# D5035-05.net
KiCad netlist of a schematic drawn in Altium Designer
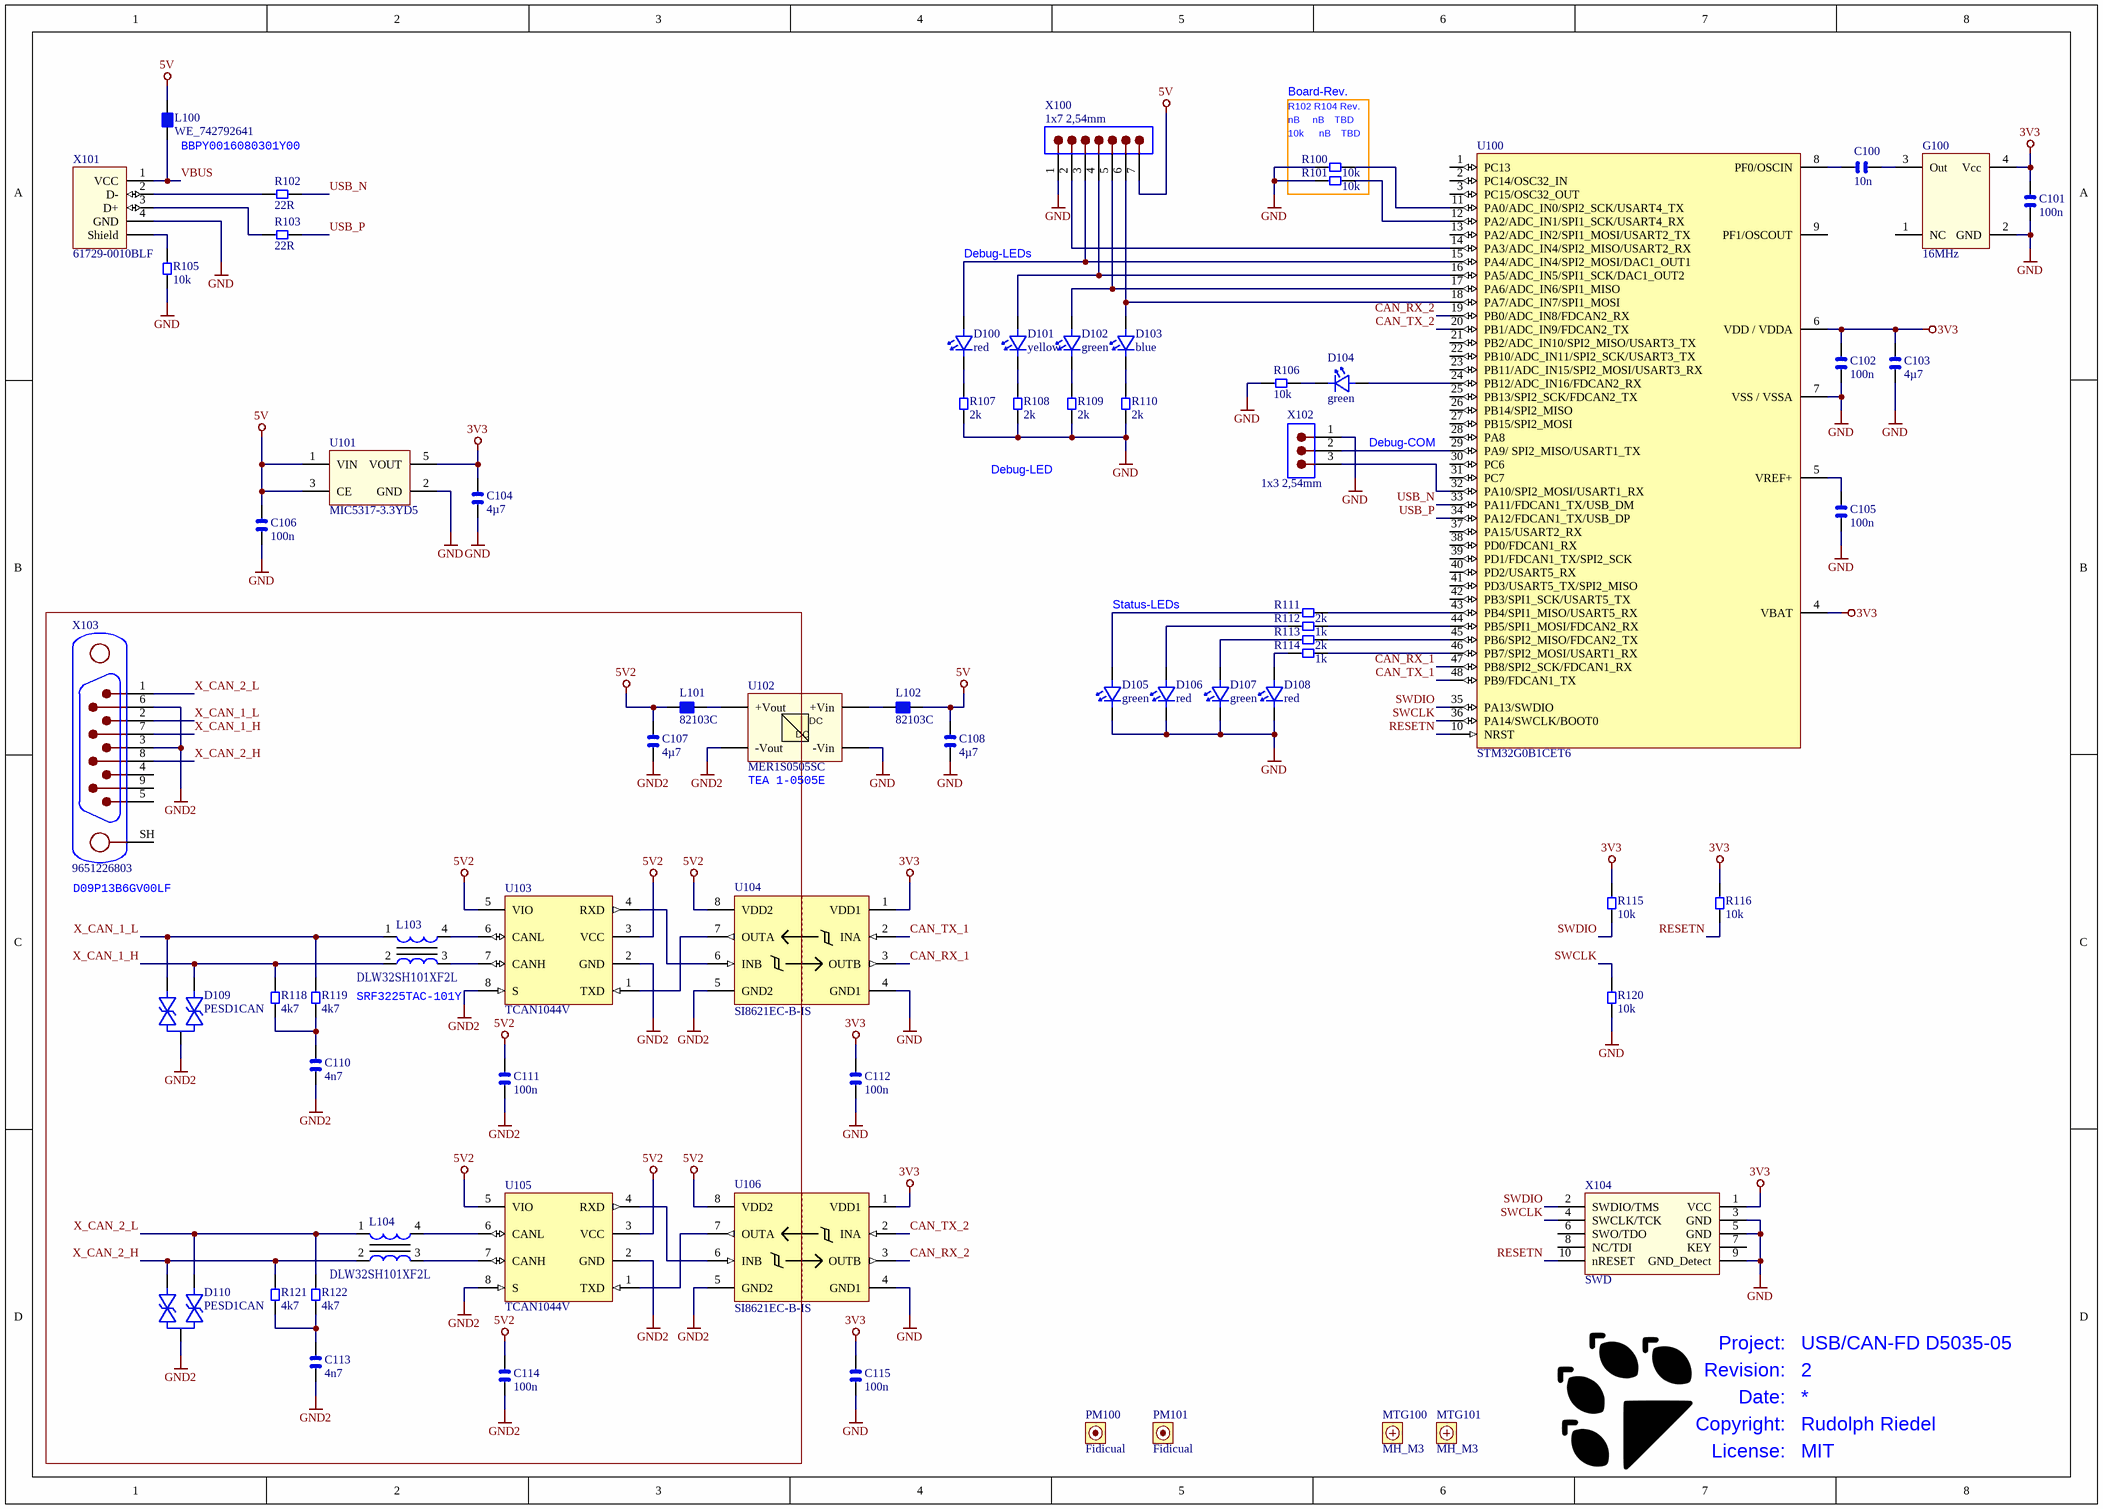
[diagram p0: D5035-05.SchDoc]

(export (version "E")
  (design (tool "Eeschema 10.0.6"))
  (components
    (comp (ref "C100")
      (value "10n")
      (footprint "CAPC1608X09L")
      (description "0603 Chip Capacitor")
      (fields (field (name "PART NUMBER") "CAPC_0603") (field (name "EDITOR") "rriedel"))
      (libsource (lib "HW-Labor_GF") (part "CAP_2_V2"))
    )
    (comp (ref "C101")
      (value "100n")
      (footprint "CAPC1608X09L")
      (description "0603 Chip Capacitor")
      (fields (field (name "PART NUMBER") "CAPC_0603") (field (name "EDITOR") "rriedel"))
      (libsource (lib "HW-Labor_GF") (part "CAP_2_V2"))
    )
    (comp (ref "C102")
      (value "100n")
      (footprint "CAPC1608X09L")
      (description "0603 Chip Capacitor")
      (fields (field (name "PART NUMBER") "CAPC_0603") (field (name "EDITOR") "rriedel"))
      (libsource (lib "HW-Labor_GF") (part "CAP_2_V2"))
    )
    (comp (ref "C103")
      (value "4µ7")
      (footprint "CAPC2012X14L")
      (description "0805 Chip Capacitor")
      (fields (field (name "PART NUMBER") "CAPC_0805") (field (name "EDITOR") "rriedel"))
      (libsource (lib "HW-Labor_GF") (part "CAP_2_V2"))
    )
    (comp (ref "C104")
      (value "4µ7")
      (footprint "CAPC2012X14L")
      (description "0805 Chip Capacitor")
      (fields (field (name "PART NUMBER") "CAPC_0805") (field (name "EDITOR") "rriedel"))
      (libsource (lib "HW-Labor_GF") (part "CAP_2_V2"))
    )
    (comp (ref "C105")
      (value "100n")
      (footprint "CAPC1608X09L")
      (description "0603 Chip Capacitor")
      (fields (field (name "PART NUMBER") "CAPC_0603") (field (name "EDITOR") "rriedel"))
      (libsource (lib "HW-Labor_GF") (part "CAP_2_V2"))
    )
    (comp (ref "C106")
      (value "100n")
      (footprint "CAPC1608X09L")
      (description "0603 Chip Capacitor")
      (fields (field (name "PART NUMBER") "CAPC_0603") (field (name "EDITOR") "rriedel"))
      (libsource (lib "HW-Labor_GF") (part "CAP_2_V2"))
    )
    (comp (ref "C107")
      (value "4µ7")
      (footprint "CAPC2012X14L")
      (description "0805 Chip Capacitor")
      (fields (field (name "PART NUMBER") "CAPC_0805") (field (name "EDITOR") "rriedel"))
      (libsource (lib "HW-Labor_GF") (part "CAP_2_V2"))
    )
    (comp (ref "C108")
      (value "4µ7")
      (footprint "CAPC2012X14L")
      (description "0805 Chip Capacitor")
      (fields (field (name "PART NUMBER") "CAPC_0805") (field (name "EDITOR") "rriedel"))
      (libsource (lib "HW-Labor_GF") (part "CAP_2_V2"))
    )
    (comp (ref "C110")
      (value "4n7")
      (footprint "CAPC2012X14L")
      (description "0805 Chip Capacitor")
      (fields (field (name "PART NUMBER") "CAPC_0805") (field (name "EDITOR") "rriedel"))
      (libsource (lib "HW-Labor_GF") (part "CAP_2_V2"))
    )
    (comp (ref "C111")
      (value "100n")
      (footprint "CAPC1608X09L")
      (description "0603 Chip Capacitor")
      (fields (field (name "PART NUMBER") "CAPC_0603") (field (name "EDITOR") "rriedel"))
      (libsource (lib "HW-Labor_GF") (part "CAP_2_V2"))
    )
    (comp (ref "C112")
      (value "100n")
      (footprint "CAPC1608X09L")
      (description "0603 Chip Capacitor")
      (fields (field (name "PART NUMBER") "CAPC_0603") (field (name "EDITOR") "rriedel"))
      (libsource (lib "HW-Labor_GF") (part "CAP_2_V2"))
    )
    (comp (ref "C113")
      (value "4n7")
      (footprint "CAPC2012X14L")
      (description "0805 Chip Capacitor")
      (fields (field (name "PART NUMBER") "CAPC_0805") (field (name "EDITOR") "rriedel"))
      (libsource (lib "HW-Labor_GF") (part "CAP_2_V2"))
    )
    (comp (ref "C114")
      (value "100n")
      (footprint "CAPC1608X09L")
      (description "0603 Chip Capacitor")
      (fields (field (name "PART NUMBER") "CAPC_0603") (field (name "EDITOR") "rriedel"))
      (libsource (lib "HW-Labor_GF") (part "CAP_2_V2"))
    )
    (comp (ref "C115")
      (value "100n")
      (footprint "CAPC1608X09L")
      (description "0603 Chip Capacitor")
      (fields (field (name "PART NUMBER") "CAPC_0603") (field (name "EDITOR") "rriedel"))
      (libsource (lib "HW-Labor_GF") (part "CAP_2_V2"))
    )
    (comp (ref "D100")
      (value "red")
      (footprint "DIOC1608X06N_LED")
      (description "LED, 0603")
      (fields (field (name "PART NUMBER") "LED_0603") (field (name "EDITOR") "rriedel"))
      (libsource (lib "HW-Labor_GF") (part "LED_generic"))
    )
    (comp (ref "D101")
      (value "yellow")
      (footprint "DIOC1608X06N_LED")
      (description "LED, 0603")
      (fields (field (name "PART NUMBER") "LED_0603") (field (name "EDITOR") "rriedel"))
      (libsource (lib "HW-Labor_GF") (part "LED_generic"))
    )
    (comp (ref "D102")
      (value "green")
      (footprint "DIOC1608X06N_LED")
      (description "LED, 0603")
      (fields (field (name "PART NUMBER") "LED_0603") (field (name "EDITOR") "rriedel"))
      (libsource (lib "HW-Labor_GF") (part "LED_generic"))
    )
    (comp (ref "D103")
      (value "blue")
      (footprint "DIOC1608X06N_LED")
      (description "LED, 0603")
      (fields (field (name "PART NUMBER") "LED_0603") (field (name "EDITOR") "rriedel"))
      (libsource (lib "HW-Labor_GF") (part "LED_generic"))
    )
    (comp (ref "D104")
      (value "green")
      (footprint "DIOC1608X06N_LED")
      (description "LED, 0603")
      (fields (field (name "PART NUMBER") "LED_0603") (field (name "EDITOR") "rriedel"))
      (libsource (lib "HW-Labor_GF") (part "LED_generic"))
    )
    (comp (ref "D105")
      (value "green")
      (footprint "DIOC1608X06N_LED")
      (description "LED, 0603")
      (fields (field (name "PART NUMBER") "LED_0603") (field (name "EDITOR") "rriedel"))
      (libsource (lib "HW-Labor_GF") (part "LED_generic"))
    )
    (comp (ref "D106")
      (value "red")
      (footprint "DIOC1608X06N_LED")
      (description "LED, 0603")
      (fields (field (name "PART NUMBER") "LED_0603") (field (name "EDITOR") "rriedel"))
      (libsource (lib "HW-Labor_GF") (part "LED_generic"))
    )
    (comp (ref "D107")
      (value "green")
      (footprint "DIOC1608X06N_LED")
      (description "LED, 0603")
      (fields (field (name "PART NUMBER") "LED_0603") (field (name "EDITOR") "rriedel"))
      (libsource (lib "HW-Labor_GF") (part "LED_generic"))
    )
    (comp (ref "D108")
      (value "red")
      (footprint "DIOC1608X06N_LED")
      (description "LED, 0603")
      (fields (field (name "PART NUMBER") "LED_0603") (field (name "EDITOR") "rriedel"))
      (libsource (lib "HW-Labor_GF") (part "LED_generic"))
    )
    (comp (ref "D109")
      (value "PESD1CAN")
      (footprint "SOT95P280X110-3N")
      (description "CAN bus ESD protection diode")
      (fields
        (field (name "MANUFACTURER") "Nexperia")
        (field (name "DISTRIBUTOR_1_PART_NUMBER") "1727-3817-1-ND")
        (field (name "EDITOR") "rriedel")
      )
      (libsource (lib "HW-Labor_GF") (part "PESD1CAN"))
    )
    (comp (ref "D110")
      (value "PESD1CAN")
      (footprint "SOT95P280X110-3N")
      (description "CAN bus ESD protection diode")
      (fields
        (field (name "MANUFACTURER") "Nexperia")
        (field (name "DISTRIBUTOR_1_PART_NUMBER") "1727-3817-1-ND")
        (field (name "EDITOR") "rriedel")
      )
      (libsource (lib "HW-Labor_GF") (part "PESD1CAN"))
    )
    (comp (ref "G100")
      (value "16MHz")
      (footprint "TG2520")
      (description "16MHz Oscillator, +/- 0.5ppm")
      (fields
        (field (name "PART NUMBER") "TG2520SMN16.0000M-MCGNNM")
        (field (name "MANUFACTURER") "Epson")
        (field (name "EDITOR") "rriedel")
      )
      (libsource (lib "HW-Labor_GF") (part "TG2520"))
    )
    (comp (ref "L100")
      (value "WE_742792641")
      (footprint "INDC1608X06L")
      (description "SMT EMI suppression ferrite bead WE-CBF")
      (fields
        (field (name "MANUFACTURER") "Wuerth")
        (field (name "DISTRIBUTOR_1_PART_NUMBER") "732-1592-1-ND")
        (field (name "EDITOR") "rriedel")
      )
      (libsource (lib "HW-Labor_GF") (part "IND_2_V1"))
    )
    (comp (ref "L101")
      (value "82103C")
      (footprint "Murata_8200C")
      (description "10µH, 0,5A, 400mR")
      (fields
        (field (name "MANUFACTURER") "Murata")
        (field (name "DISTRIBUTOR_1_PART_NUMBER") "811-2473-1-ND")
        (field (name "EDITOR") "rriedel")
      )
      (libsource (lib "HW-Labor_GF") (part "IND_2_V1"))
    )
    (comp (ref "L102")
      (value "82103C")
      (footprint "Murata_8200C")
      (description "10µH, 0,5A, 400mR")
      (fields
        (field (name "MANUFACTURER") "Murata")
        (field (name "DISTRIBUTOR_1_PART_NUMBER") "811-2473-1-ND")
        (field (name "EDITOR") "rriedel")
      )
      (libsource (lib "HW-Labor_GF") (part "IND_2_V1"))
    )
    (comp (ref "L103")
      (value "DLW32SH101XF2L‎")
      (footprint "ACT1210")
      (description "Common Mode Filter,  -50°C ... +150°C, AEC-Q200")
      (fields
        (field (name "PART NUMBER") "ACT1210-101-2P-TL00")
        (field (name "MANUFACTURER") "TDK")
        (field (name "EDITOR") "rriedel")
      )
      (libsource (lib "HW-Labor_GF") (part "CAN_DROSSEL"))
    )
    (comp (ref "L104")
      (value "DLW32SH101XF2L‎")
      (footprint "ACT1210")
      (description "Common Mode Filter,  -50°C ... +150°C, AEC-Q200")
      (fields
        (field (name "PART NUMBER") "ACT1210-101-2P-TL00")
        (field (name "MANUFACTURER") "TDK")
        (field (name "EDITOR") "rriedel")
      )
      (libsource (lib "HW-Labor_GF") (part "CAN_DROSSEL"))
    )
    (comp (ref "MTG100")
      (value "MH_M3")
      (footprint "HOLE_3_2MM")
      (description "Mounting-Hole for M3 screws")
      (fields (field (name "EDITOR") "rriedel"))
      (libsource (lib "HW-Labor_GF") (part "MTG_V1"))
    )
    (comp (ref "MTG101")
      (value "MH_M3")
      (footprint "HOLE_3_2MM")
      (description "Mounting-Hole for M3 screws")
      (fields (field (name "EDITOR") "rriedel"))
      (libsource (lib "HW-Labor_GF") (part "MTG_V1"))
    )
    (comp (ref "PM100")
      (value "Fidicual")
      (footprint "PM100")
      (fields (field (name "PART NUMBER") "PM100") (field (name "EDITOR") "rriedel"))
      (libsource (lib "HW-Labor_GF") (part "PM100"))
    )
    (comp (ref "PM101")
      (value "Fidicual")
      (footprint "PM100")
      (fields (field (name "PART NUMBER") "PM100") (field (name "EDITOR") "rriedel"))
      (libsource (lib "HW-Labor_GF") (part "PM100"))
    )
    (comp (ref "R100")
      (value "10k")
      (footprint "RESC1608X06L")
      (description "0603 Chip Resistor")
      (fields (field (name "PART NUMBER") "RESC_0603") (field (name "EDITOR") "rriedel"))
      (libsource (lib "HW-Labor_GF") (part "RES_2_V2"))
    )
    (comp (ref "R101")
      (value "10k")
      (footprint "RESC1608X06L")
      (description "0603 Chip Resistor")
      (fields (field (name "PART NUMBER") "RESC_0603") (field (name "EDITOR") "rriedel"))
      (libsource (lib "HW-Labor_GF") (part "RES_2_V2"))
    )
    (comp (ref "R102")
      (value "22R")
      (footprint "RESC1608X06L")
      (description "0603 Chip Resistor")
      (fields (field (name "PART NUMBER") "RESC_0603") (field (name "EDITOR") "rriedel"))
      (libsource (lib "HW-Labor_GF") (part "RES_2_V2"))
    )
    (comp (ref "R103")
      (value "22R")
      (footprint "RESC1608X06L")
      (description "0603 Chip Resistor")
      (fields (field (name "PART NUMBER") "RESC_0603") (field (name "EDITOR") "rriedel"))
      (libsource (lib "HW-Labor_GF") (part "RES_2_V2"))
    )
    (comp (ref "R105")
      (value "10k")
      (footprint "RESC1608X06L")
      (description "0603 Chip Resistor")
      (fields (field (name "PART NUMBER") "RESC_0603") (field (name "EDITOR") "rriedel"))
      (libsource (lib "HW-Labor_GF") (part "RES_2_V2"))
    )
    (comp (ref "R106")
      (value "10k")
      (footprint "RESC1608X06L")
      (description "0603 Chip Resistor")
      (fields (field (name "PART NUMBER") "RESC_0603") (field (name "EDITOR") "rriedel"))
      (libsource (lib "HW-Labor_GF") (part "RES_2_V2"))
    )
    (comp (ref "R107")
      (value "2k")
      (footprint "RESC1608X06L")
      (description "0603 Chip Resistor")
      (fields (field (name "PART NUMBER") "RESC_0603") (field (name "EDITOR") "rriedel"))
      (libsource (lib "HW-Labor_GF") (part "RES_2_V2"))
    )
    (comp (ref "R108")
      (value "2k")
      (footprint "RESC1608X06L")
      (description "0603 Chip Resistor")
      (fields (field (name "PART NUMBER") "RESC_0603") (field (name "EDITOR") "rriedel"))
      (libsource (lib "HW-Labor_GF") (part "RES_2_V2"))
    )
    (comp (ref "R109")
      (value "2k")
      (footprint "RESC1608X06L")
      (description "0603 Chip Resistor")
      (fields (field (name "PART NUMBER") "RESC_0603") (field (name "EDITOR") "rriedel"))
      (libsource (lib "HW-Labor_GF") (part "RES_2_V2"))
    )
    (comp (ref "R110")
      (value "2k")
      (footprint "RESC1608X06L")
      (description "0603 Chip Resistor")
      (fields (field (name "PART NUMBER") "RESC_0603") (field (name "EDITOR") "rriedel"))
      (libsource (lib "HW-Labor_GF") (part "RES_2_V2"))
    )
    (comp (ref "R111")
      (value "2k")
      (footprint "RESC1608X06L")
      (description "0603 Chip Resistor")
      (fields (field (name "PART NUMBER") "RESC_0603") (field (name "EDITOR") "rriedel"))
      (libsource (lib "HW-Labor_GF") (part "RES_2_V2"))
    )
    (comp (ref "R112")
      (value "1k")
      (footprint "RESC1608X06L")
      (description "0603 Chip Resistor")
      (fields (field (name "PART NUMBER") "RESC_0603") (field (name "EDITOR") "rriedel"))
      (libsource (lib "HW-Labor_GF") (part "RES_2_V2"))
    )
    (comp (ref "R113")
      (value "2k")
      (footprint "RESC1608X06L")
      (description "0603 Chip Resistor")
      (fields (field (name "PART NUMBER") "RESC_0603") (field (name "EDITOR") "rriedel"))
      (libsource (lib "HW-Labor_GF") (part "RES_2_V2"))
    )
    (comp (ref "R114")
      (value "1k")
      (footprint "RESC1608X06L")
      (description "0603 Chip Resistor")
      (fields (field (name "PART NUMBER") "RESC_0603") (field (name "EDITOR") "rriedel"))
      (libsource (lib "HW-Labor_GF") (part "RES_2_V2"))
    )
    (comp (ref "R115")
      (value "10k")
      (footprint "RESC1608X06L")
      (description "0603 Chip Resistor")
      (fields (field (name "PART NUMBER") "RESC_0603") (field (name "EDITOR") "rriedel"))
      (libsource (lib "HW-Labor_GF") (part "RES_2_V2"))
    )
    (comp (ref "R116")
      (value "10k")
      (footprint "RESC1608X06L")
      (description "0603 Chip Resistor")
      (fields (field (name "PART NUMBER") "RESC_0603") (field (name "EDITOR") "rriedel"))
      (libsource (lib "HW-Labor_GF") (part "RES_2_V2"))
    )
    (comp (ref "R118")
      (value "4k7")
      (footprint "RESC2012X06L")
      (description "0805 Chip Resistor")
      (fields (field (name "PART NUMBER") "RESC_0805") (field (name "EDITOR") "rriedel"))
      (libsource (lib "HW-Labor_GF") (part "RES_2_V2"))
    )
    (comp (ref "R119")
      (value "4k7")
      (footprint "RESC2012X06L")
      (description "0805 Chip Resistor")
      (fields (field (name "PART NUMBER") "RESC_0805") (field (name "EDITOR") "rriedel"))
      (libsource (lib "HW-Labor_GF") (part "RES_2_V2"))
    )
    (comp (ref "R120")
      (value "10k")
      (footprint "RESC1608X06L")
      (description "0603 Chip Resistor")
      (fields (field (name "PART NUMBER") "RESC_0603") (field (name "EDITOR") "rriedel"))
      (libsource (lib "HW-Labor_GF") (part "RES_2_V2"))
    )
    (comp (ref "R121")
      (value "4k7")
      (footprint "RESC2012X06L")
      (description "0805 Chip Resistor")
      (fields (field (name "PART NUMBER") "RESC_0805") (field (name "EDITOR") "rriedel"))
      (libsource (lib "HW-Labor_GF") (part "RES_2_V2"))
    )
    (comp (ref "R122")
      (value "4k7")
      (footprint "RESC2012X06L")
      (description "0805 Chip Resistor")
      (fields (field (name "PART NUMBER") "RESC_0805") (field (name "EDITOR") "rriedel"))
      (libsource (lib "HW-Labor_GF") (part "RES_2_V2"))
    )
    (comp (ref "U100")
      (value "STM32G0B1CET6")
      (footprint "TQFP50P900X900X120-48N")
      (description "32-bit Microcontroller, 64MHz Cortex M0+, 512k FLASH,  USB")
      (fields
        (field (name "MANUFACTURER") "STM")
        (field (name "DISTRIBUTOR_1_PART_NUMBER") "511-STM32G0B1CET6")
        (field (name "EDITOR") "rriedel")
      )
      (libsource (lib "HW-Labor_GF") (part "STM32G0B1CxTx"))
    )
    (comp (ref "U101")
      (value "MIC5317-3.3YD5")
      (footprint "SOT95P280X110-5N")
      (description "100 mA LDO,  Vout= 3,3V, -40°C..125°C")
      (fields
        (field (name "PART NUMBER") "MIC5233-3.3")
        (field (name "MANUFACTURER") "Microchip")
        (field (name "EDITOR") "rriedel")
      )
      (libsource (lib "HW-Labor_GF") (part "LDO_SOT23-5"))
    )
    (comp (ref "U102")
      (value "MER1S0505SC")
      (footprint "MER1SxxxxC")
      (description "Isolated 1W Single Output DC-DC Converters 5V/5V 200mA")
      (fields
        (field (name "MANUFACTURER") "Murata")
        (field (name "DISTRIBUTOR_1_PART_NUMBER") "811-2124-5-ND‎")
        (field (name "EDITOR") "rriedel")
      )
      (libsource (lib "HW-Labor_GF") (part "MER1SxxxxC"))
    )
    (comp (ref "U103")
      (value "TCAN1044V")
      (footprint "SOT65P280X100-8N")
      (description "CAN-FD transceiver 8MBit, VIO Pin")
      (fields
        (field (name "MANUFACTURER") "TI")
        (field (name "DISTRIBUTOR_1_PART_NUMBER") "296-TCAN1044VDDFRCT-ND")
        (field (name "EDITOR") "rriedel")
      )
      (libsource (lib "HW-Labor_GF") (part "TJA1051T_3"))
    )
    (comp (ref "U104")
      (value "SI8621EC-B-IS")
      (footprint "SOIC127P600X175-8N")
      (description "Dual channel digital isolator, 150Mbit, 3,75kV")
      (fields
        (field (name "MANUFACTURER") "Silicon Labs")
        (field (name "DISTRIBUTOR_1_PART_NUMBER") "336-4776-1-ND")
        (field (name "EDITOR") "rriedel")
      )
      (libsource (lib "HW-Labor_GF") (part "SI8621"))
    )
    (comp (ref "U105")
      (value "TCAN1044V")
      (footprint "SOT65P280X100-8N")
      (description "CAN-FD transceiver 8MBit, VIO Pin")
      (fields
        (field (name "MANUFACTURER") "TI")
        (field (name "DISTRIBUTOR_1_PART_NUMBER") "296-TCAN1044VDDFRCT-ND")
        (field (name "EDITOR") "rriedel")
      )
      (libsource (lib "HW-Labor_GF") (part "TJA1051T_3"))
    )
    (comp (ref "U106")
      (value "SI8621EC-B-IS")
      (footprint "SOIC127P600X175-8N")
      (description "Dual channel digital isolator, 150Mbit, 3,75kV")
      (fields
        (field (name "MANUFACTURER") "Silicon Labs")
        (field (name "DISTRIBUTOR_1_PART_NUMBER") "336-4776-1-ND")
        (field (name "EDITOR") "rriedel")
      )
      (libsource (lib "HW-Labor_GF") (part "SI8621"))
    )
    (comp (ref "X100")
      (value "1x7 2,54mm")
      (footprint "PINH_1x07_2_54mm")
      (description "Pin-Header 2,54 mm 7pins")
      (fields (field (name "PART NUMBER") "PINH_1x7_2_54") (field (name "EDITOR") "rriedel"))
      (libsource (lib "HW-Labor_GF") (part "CONM_1x7_V2"))
    )
    (comp (ref "X101")
      (value "61729-0010BLF")
      (footprint "61729-xxxxxLF")
      (description "USB-B socket, THT")
      (fields
        (field (name "MANUFACTURER") "Amphenol")
        (field (name "DISTRIBUTOR_1_PART_NUMBER") "609-1039-ND")
        (field (name "EDITOR") "rriedel")
      )
      (libsource (lib "HW-Labor_GF") (part "USB"))
    )
    (comp (ref "X102")
      (value "1x3 2,54mm")
      (footprint "PINH_1x03_2_54mm")
      (description "Pin-Header 2,54 mm 3pins")
      (fields (field (name "PART NUMBER") "PINH_1x3_2_54") (field (name "EDITOR") "rriedel"))
      (libsource (lib "HW-Labor_GF") (part "CONM_1x3_V2"))
    )
    (comp (ref "X103")
      (value "9651226803")
      (footprint "09651226803")
      (description "D-Sub, 9 pin, male, right angle")
      (fields
        (field (name "MANUFACTURER") "Harting")
        (field (name "DISTRIBUTOR_1_PART_NUMBER") "2752007")
        (field (name "EDITOR") "rriedel")
      )
      (libsource (lib "HW-Labor_GF") (part "D_Sub_9_Male"))
    )
    (comp (ref "X104")
      (value "SWD")
      (footprint "FTSH-105-01-L-DV-K")
      (description "ARM Debug-Header 2x5 1,27 mm")
      (fields (field (name "EDITOR") "rriedel"))
      (libsource (lib "HW-Labor_GF") (part "SWD"))
    )
  )
  (nets
    (net (code "1") (name "/CAN_RX_1") (class "Default")
      (node (ref "U100") (pin "47") (pinfunction "PB8/SPI2_SCK/FDCAN1_RX_47") (pintype "bidirectional"))
      (node (ref "U104") (pin "3") (pinfunction "OUTB_3") (pintype "output"))
    )
    (net (code "2") (name "/CAN_RX_2") (class "Default")
      (node (ref "U100") (pin "19") (pinfunction "PB0/ADC_IN8/FDCAN2_RX_19") (pintype "bidirectional"))
      (node (ref "U106") (pin "3") (pinfunction "OUTB_3") (pintype "output"))
    )
    (net (code "3") (name "/CAN_TX_1") (class "Default")
      (node (ref "U100") (pin "48") (pinfunction "PB9/FDCAN1_TX_48") (pintype "bidirectional"))
      (node (ref "U104") (pin "2") (pinfunction "INA_2") (pintype "input"))
    )
    (net (code "4") (name "/CAN_TX_2") (class "Default")
      (node (ref "U100") (pin "20") (pinfunction "PB1/ADC_IN9/FDCAN2_TX_20") (pintype "bidirectional"))
      (node (ref "U106") (pin "2") (pinfunction "INA_2") (pintype "input"))
    )
    (net (code "5") (name "/RESETN") (class "Default")
      (node (ref "R116") (pin "1") (pinfunction "1_1") (pintype "passive"))
      (node (ref "U100") (pin "10") (pinfunction "NRST_10") (pintype "input"))
      (node (ref "X104") (pin "10") (pinfunction "nRESET_10") (pintype "passive"))
    )
    (net (code "6") (name "/SWCLK") (class "Default")
      (node (ref "R120") (pin "2") (pinfunction "2_2") (pintype "passive"))
      (node (ref "U100") (pin "36") (pinfunction "PA14/SWCLK/BOOT0_36") (pintype "bidirectional"))
      (node (ref "X104") (pin "4") (pinfunction "SWCLK/TCK_4") (pintype "passive"))
    )
    (net (code "7") (name "/SWDIO") (class "Default")
      (node (ref "R115") (pin "1") (pinfunction "1_1") (pintype "passive"))
      (node (ref "U100") (pin "35") (pinfunction "PA13/SWDIO_35") (pintype "bidirectional"))
      (node (ref "X104") (pin "2") (pinfunction "SWDIO/TMS_2") (pintype "passive"))
    )
    (net (code "8") (name "/USB_N") (class "Default")
      (node (ref "R102") (pin "2") (pinfunction "2_2") (pintype "passive"))
      (node (ref "U100") (pin "33") (pinfunction "PA11/FDCAN1_TX/USB_DM_33") (pintype "bidirectional"))
    )
    (net (code "9") (name "/USB_P") (class "Default")
      (node (ref "R103") (pin "2") (pinfunction "2_2") (pintype "passive"))
      (node (ref "U100") (pin "34") (pinfunction "PA12/FDCAN1_TX/USB_DP_34") (pintype "bidirectional"))
    )
    (net (code "10") (name "/VBUS") (class "Default")
      (node (ref "L100") (pin "1") (pinfunction "1_1") (pintype "passive"))
      (node (ref "X101") (pin "1") (pinfunction "VCC_1") (pintype "power_in"))
    )
    (net (code "11") (name "/X_CAN_1_H") (class "Default")
      (node (ref "D109") (pin "2") (pinfunction "2_2") (pintype "passive"))
      (node (ref "L103") (pin "2") (pintype "passive"))
      (node (ref "R118") (pin "2") (pinfunction "2_2") (pintype "passive"))
      (node (ref "X103") (pin "7") (pinfunction "7_7") (pintype "passive"))
    )
    (net (code "12") (name "/X_CAN_1_L") (class "Default")
      (node (ref "D109") (pin "1") (pinfunction "1_1") (pintype "passive"))
      (node (ref "L103") (pin "1") (pintype "passive"))
      (node (ref "R119") (pin "2") (pinfunction "2_2") (pintype "passive"))
      (node (ref "X103") (pin "2") (pinfunction "2_2") (pintype "passive"))
    )
    (net (code "13") (name "/X_CAN_2_H") (class "Default")
      (node (ref "D110") (pin "1") (pinfunction "1_1") (pintype "passive"))
      (node (ref "L104") (pin "2") (pintype "passive"))
      (node (ref "R121") (pin "2") (pinfunction "2_2") (pintype "passive"))
      (node (ref "X103") (pin "8") (pinfunction "8_8") (pintype "passive"))
    )
    (net (code "14") (name "/X_CAN_2_L") (class "Default")
      (node (ref "D110") (pin "2") (pinfunction "2_2") (pintype "passive"))
      (node (ref "L104") (pin "1") (pintype "passive"))
      (node (ref "R122") (pin "2") (pinfunction "2_2") (pintype "passive"))
      (node (ref "X103") (pin "1") (pinfunction "1_1") (pintype "passive"))
    )
    (net (code "15") (name "3V3") (class "Default")
      (node (ref "C101") (pin "2") (pinfunction "2_2") (pintype "passive"))
      (node (ref "C102") (pin "2") (pinfunction "2_2") (pintype "passive"))
      (node (ref "C103") (pin "2") (pinfunction "2_2") (pintype "passive"))
      (node (ref "C104") (pin "2") (pinfunction "2_2") (pintype "passive"))
      (node (ref "C112") (pin "2") (pinfunction "2_2") (pintype "passive"))
      (node (ref "C115") (pin "2") (pinfunction "2_2") (pintype "passive"))
      (node (ref "G100") (pin "4") (pinfunction "Vcc_4") (pintype "passive"))
      (node (ref "R115") (pin "2") (pinfunction "2_2") (pintype "passive"))
      (node (ref "R116") (pin "2") (pinfunction "2_2") (pintype "passive"))
      (node (ref "U100") (pin "4") (pinfunction "VBAT_4") (pintype "power_in"))
      (node (ref "U100") (pin "6") (pinfunction "VDD_/_VDDA_6") (pintype "power_in"))
      (node (ref "U101") (pin "5") (pinfunction "VOUT_5") (pintype "passive"))
      (node (ref "U104") (pin "1") (pinfunction "VDD1_1") (pintype "power_in"))
      (node (ref "U106") (pin "1") (pinfunction "VDD1_1") (pintype "power_in"))
      (node (ref "X104") (pin "1") (pinfunction "VCC_1") (pintype "power_in"))
    )
    (net (code "16") (name "5V") (class "Default")
      (node (ref "C106") (pin "2") (pinfunction "2_2") (pintype "passive"))
      (node (ref "C108") (pin "2") (pinfunction "2_2") (pintype "passive"))
      (node (ref "L100") (pin "2") (pinfunction "2_2") (pintype "passive"))
      (node (ref "L102") (pin "1") (pinfunction "1_1") (pintype "passive"))
      (node (ref "U101") (pin "1") (pinfunction "VIN_1") (pintype "passive"))
      (node (ref "U101") (pin "3") (pinfunction "CE_3") (pintype "passive"))
      (node (ref "X100") (pin "7") (pinfunction "7_7") (pintype "passive"))
    )
    (net (code "17") (name "5V2") (class "Default")
      (node (ref "C107") (pin "2") (pinfunction "2_2") (pintype "passive"))
      (node (ref "C111") (pin "2") (pinfunction "2_2") (pintype "passive"))
      (node (ref "C114") (pin "2") (pinfunction "2_2") (pintype "passive"))
      (node (ref "L101") (pin "2") (pinfunction "2_2") (pintype "passive"))
      (node (ref "U103") (pin "3") (pinfunction "VCC_3") (pintype "power_in"))
      (node (ref "U103") (pin "5") (pinfunction "VIO_5") (pintype "power_in"))
      (node (ref "U104") (pin "8") (pinfunction "VDD2_8") (pintype "power_in"))
      (node (ref "U105") (pin "3") (pinfunction "VCC_3") (pintype "power_in"))
      (node (ref "U105") (pin "5") (pinfunction "VIO_5") (pintype "power_in"))
      (node (ref "U106") (pin "8") (pinfunction "VDD2_8") (pintype "power_in"))
    )
    (net (code "18") (name "GND") (class "Default")
      (node (ref "C101") (pin "1") (pinfunction "1_1") (pintype "passive"))
      (node (ref "C102") (pin "1") (pinfunction "1_1") (pintype "passive"))
      (node (ref "C103") (pin "1") (pinfunction "1_1") (pintype "passive"))
      (node (ref "C104") (pin "1") (pinfunction "1_1") (pintype "passive"))
      (node (ref "C105") (pin "1") (pinfunction "1_1") (pintype "passive"))
      (node (ref "C106") (pin "1") (pinfunction "1_1") (pintype "passive"))
      (node (ref "C108") (pin "1") (pinfunction "1_1") (pintype "passive"))
      (node (ref "C112") (pin "1") (pinfunction "1_1") (pintype "passive"))
      (node (ref "C115") (pin "1") (pinfunction "1_1") (pintype "passive"))
      (node (ref "D105") (pin "1") (pinfunction "1_1") (pintype "passive"))
      (node (ref "D106") (pin "1") (pinfunction "1_1") (pintype "passive"))
      (node (ref "D107") (pin "1") (pinfunction "1_1") (pintype "passive"))
      (node (ref "D108") (pin "1") (pinfunction "1_1") (pintype "passive"))
      (node (ref "G100") (pin "2") (pinfunction "GND_2") (pintype "power_in"))
      (node (ref "R100") (pin "2") (pinfunction "2_2") (pintype "passive"))
      (node (ref "R101") (pin "2") (pinfunction "2_2") (pintype "passive"))
      (node (ref "R105") (pin "1") (pinfunction "1_1") (pintype "passive"))
      (node (ref "R106") (pin "1") (pinfunction "1_1") (pintype "passive"))
      (node (ref "R107") (pin "1") (pinfunction "1_1") (pintype "passive"))
      (node (ref "R108") (pin "1") (pinfunction "1_1") (pintype "passive"))
      (node (ref "R109") (pin "1") (pinfunction "1_1") (pintype "passive"))
      (node (ref "R110") (pin "1") (pinfunction "1_1") (pintype "passive"))
      (node (ref "R120") (pin "1") (pinfunction "1_1") (pintype "passive"))
      (node (ref "U100") (pin "7") (pinfunction "VSS_/_VSSA_7") (pintype "power_in"))
      (node (ref "U101") (pin "2") (pinfunction "GND_2") (pintype "passive"))
      (node (ref "U102") (pin "2") (pinfunction "-Vin_2") (pintype "power_in"))
      (node (ref "U104") (pin "4") (pinfunction "GND1_4") (pintype "power_in"))
      (node (ref "U106") (pin "4") (pinfunction "GND1_4") (pintype "power_in"))
      (node (ref "X100") (pin "1") (pinfunction "1_1") (pintype "passive"))
      (node (ref "X101") (pin "4") (pinfunction "GND_4") (pintype "power_in"))
      (node (ref "X102") (pin "1") (pinfunction "1_1") (pintype "passive"))
      (node (ref "X104") (pin "3") (pinfunction "GND_3") (pintype "power_in"))
      (node (ref "X104") (pin "5") (pinfunction "GND_5") (pintype "power_in"))
      (node (ref "X104") (pin "9") (pinfunction "GND_Detect_9") (pintype "power_in"))
    )
    (net (code "19") (name "GND2") (class "Default")
      (node (ref "C107") (pin "1") (pinfunction "1_1") (pintype "passive"))
      (node (ref "C110") (pin "1") (pinfunction "1_1") (pintype "passive"))
      (node (ref "C111") (pin "1") (pinfunction "1_1") (pintype "passive"))
      (node (ref "C113") (pin "1") (pinfunction "1_1") (pintype "passive"))
      (node (ref "C114") (pin "1") (pinfunction "1_1") (pintype "passive"))
      (node (ref "D109") (pin "3") (pinfunction "3_3") (pintype "passive"))
      (node (ref "D110") (pin "3") (pinfunction "3_3") (pintype "passive"))
      (node (ref "U102") (pin "4") (pinfunction "-Vout_4") (pintype "power_in"))
      (node (ref "U103") (pin "2") (pinfunction "GND_2") (pintype "power_in"))
      (node (ref "U103") (pin "8") (pinfunction "S_8") (pintype "input"))
      (node (ref "U104") (pin "5") (pinfunction "GND2_5") (pintype "power_in"))
      (node (ref "U105") (pin "2") (pinfunction "GND_2") (pintype "power_in"))
      (node (ref "U105") (pin "8") (pinfunction "S_8") (pintype "input"))
      (node (ref "U106") (pin "5") (pinfunction "GND2_5") (pintype "power_in"))
      (node (ref "X103") (pin "3") (pinfunction "3_3") (pintype "passive"))
      (node (ref "X103") (pin "6") (pinfunction "6_6") (pintype "passive"))
    )
    (net (code "20") (name "Net-(C110-Pad2)") (class "Default")
      (node (ref "C110") (pin "2") (pinfunction "2_2") (pintype "passive"))
      (node (ref "R118") (pin "1") (pinfunction "1_1") (pintype "passive"))
      (node (ref "R119") (pin "1") (pinfunction "1_1") (pintype "passive"))
    )
    (net (code "21") (name "Net-(C113-Pad2)") (class "Default")
      (node (ref "C113") (pin "2") (pinfunction "2_2") (pintype "passive"))
      (node (ref "R121") (pin "1") (pinfunction "1_1") (pintype "passive"))
      (node (ref "R122") (pin "1") (pinfunction "1_1") (pintype "passive"))
    )
    (net (code "22") (name "Net-(D100-Pad1)") (class "Default")
      (node (ref "D100") (pin "1") (pinfunction "1_1") (pintype "passive"))
      (node (ref "R107") (pin "2") (pinfunction "2_2") (pintype "passive"))
    )
    (net (code "23") (name "Net-(D101-Pad1)") (class "Default")
      (node (ref "D101") (pin "1") (pinfunction "1_1") (pintype "passive"))
      (node (ref "R108") (pin "2") (pinfunction "2_2") (pintype "passive"))
    )
    (net (code "24") (name "Net-(D102-Pad1)") (class "Default")
      (node (ref "D102") (pin "1") (pinfunction "1_1") (pintype "passive"))
      (node (ref "R109") (pin "2") (pinfunction "2_2") (pintype "passive"))
    )
    (net (code "25") (name "Net-(D103-Pad1)") (class "Default")
      (node (ref "D103") (pin "1") (pinfunction "1_1") (pintype "passive"))
      (node (ref "R110") (pin "2") (pinfunction "2_2") (pintype "passive"))
    )
    (net (code "26") (name "Net-(D104-Pad1)") (class "Default")
      (node (ref "D104") (pin "1") (pinfunction "1_1") (pintype "passive"))
      (node (ref "R106") (pin "2") (pinfunction "2_2") (pintype "passive"))
    )
    (net (code "27") (name "Net-(D105-Pad2)") (class "Default")
      (node (ref "D105") (pin "2") (pinfunction "2_2") (pintype "passive"))
      (node (ref "R111") (pin "1") (pinfunction "1_1") (pintype "passive"))
    )
    (net (code "28") (name "Net-(D106-Pad2)") (class "Default")
      (node (ref "D106") (pin "2") (pinfunction "2_2") (pintype "passive"))
      (node (ref "R112") (pin "1") (pinfunction "1_1") (pintype "passive"))
    )
    (net (code "29") (name "Net-(D107-Pad2)") (class "Default")
      (node (ref "D107") (pin "2") (pinfunction "2_2") (pintype "passive"))
      (node (ref "R113") (pin "1") (pinfunction "1_1") (pintype "passive"))
    )
    (net (code "30") (name "Net-(D108-Pad2)") (class "Default")
      (node (ref "D108") (pin "2") (pinfunction "2_2") (pintype "passive"))
      (node (ref "R114") (pin "1") (pinfunction "1_1") (pintype "passive"))
    )
    (net (code "31") (name "Net-(G100-Out)") (class "Default")
      (node (ref "C100") (pin "2") (pinfunction "2_2") (pintype "passive"))
      (node (ref "G100") (pin "3") (pinfunction "Out_3") (pintype "passive"))
    )
    (net (code "32") (name "Net-(U100-PA0{slash}ADC_IN0{slash}SPI2_SCK{slash}USART4_TX)") (class "Default")
      (node (ref "R100") (pin "1") (pinfunction "1_1") (pintype "passive"))
      (node (ref "U100") (pin "11") (pinfunction "PA0/ADC_IN0/SPI2_SCK/USART4_TX_11") (pintype "bidirectional"))
    )
    (net (code "33") (name "Net-(U100-PA2{slash}ADC_IN1{slash}SPI1_SCK{slash}USART4_RX)") (class "Default")
      (node (ref "R101") (pin "1") (pinfunction "1_1") (pintype "passive"))
      (node (ref "U100") (pin "12") (pinfunction "PA2/ADC_IN1/SPI1_SCK/USART4_RX_12") (pintype "bidirectional"))
    )
    (net (code "34") (name "Net-(U100-PA3{slash}ADC_IN4{slash}SPI2_MISO{slash}USART2_RX)") (class "Default")
      (node (ref "U100") (pin "14") (pinfunction "PA3/ADC_IN4/SPI2_MISO/USART2_RX_14") (pintype "bidirectional"))
      (node (ref "X100") (pin "2") (pinfunction "2_2") (pintype "passive"))
    )
    (net (code "35") (name "Net-(U100-PA4{slash}ADC_IN4{slash}SPI2_MOSI{slash}DAC1_OUT1)") (class "Default")
      (node (ref "D100") (pin "2") (pinfunction "2_2") (pintype "passive"))
      (node (ref "U100") (pin "15") (pinfunction "PA4/ADC_IN4/SPI2_MOSI/DAC1_OUT1_15") (pintype "bidirectional"))
      (node (ref "X100") (pin "3") (pinfunction "3_3") (pintype "passive"))
    )
    (net (code "36") (name "Net-(U100-PA5{slash}ADC_IN5{slash}SPI1_SCK{slash}DAC1_OUT2)") (class "Default")
      (node (ref "D101") (pin "2") (pinfunction "2_2") (pintype "passive"))
      (node (ref "U100") (pin "16") (pinfunction "PA5/ADC_IN5/SPI1_SCK/DAC1_OUT2_16") (pintype "bidirectional"))
      (node (ref "X100") (pin "4") (pinfunction "4_4") (pintype "passive"))
    )
    (net (code "37") (name "Net-(U100-PA6{slash}ADC_IN6{slash}SPI1_MISO)") (class "Default")
      (node (ref "D102") (pin "2") (pinfunction "2_2") (pintype "passive"))
      (node (ref "U100") (pin "17") (pinfunction "PA6/ADC_IN6/SPI1_MISO_17") (pintype "bidirectional"))
      (node (ref "X100") (pin "5") (pinfunction "5_5") (pintype "passive"))
    )
    (net (code "38") (name "Net-(U100-PA7{slash}ADC_IN7{slash}SPI1_MOSI)") (class "Default")
      (node (ref "D103") (pin "2") (pinfunction "2_2") (pintype "passive"))
      (node (ref "U100") (pin "18") (pinfunction "PA7/ADC_IN7/SPI1_MOSI_18") (pintype "bidirectional"))
      (node (ref "X100") (pin "6") (pinfunction "6_6") (pintype "passive"))
    )
    (net (code "39") (name "Net-(U100-PA9{slash}_SPI2_MISO{slash}USART1_TX)") (class "Default")
      (node (ref "U100") (pin "29") (pinfunction "PA9/_SPI2_MISO/USART1_TX_29") (pintype "bidirectional"))
      (node (ref "X102") (pin "2") (pinfunction "2_2") (pintype "passive"))
    )
    (net (code "40") (name "Net-(U100-PA10{slash}SPI2_MOSI{slash}USART1_RX)") (class "Default")
      (node (ref "U100") (pin "32") (pinfunction "PA10/SPI2_MOSI/USART1_RX_32") (pintype "bidirectional"))
      (node (ref "X102") (pin "3") (pinfunction "3_3") (pintype "passive"))
    )
    (net (code "41") (name "Net-(U100-PB4{slash}SPI1_MISO{slash}USART5_RX)") (class "Default")
      (node (ref "R111") (pin "2") (pinfunction "2_2") (pintype "passive"))
      (node (ref "U100") (pin "43") (pinfunction "PB4/SPI1_MISO/USART5_RX_43") (pintype "bidirectional"))
    )
    (net (code "42") (name "Net-(U100-PB5{slash}SPI1_MOSI{slash}FDCAN2_RX)") (class "Default")
      (node (ref "R112") (pin "2") (pinfunction "2_2") (pintype "passive"))
      (node (ref "U100") (pin "44") (pinfunction "PB5/SPI1_MOSI/FDCAN2_RX_44") (pintype "bidirectional"))
    )
    (net (code "43") (name "Net-(U100-PB6{slash}SPI2_MISO{slash}FDCAN2_TX)") (class "Default")
      (node (ref "R113") (pin "2") (pinfunction "2_2") (pintype "passive"))
      (node (ref "U100") (pin "45") (pinfunction "PB6/SPI2_MISO/FDCAN2_TX_45") (pintype "bidirectional"))
    )
    (net (code "44") (name "Net-(U100-PB7{slash}SPI2_MOSI{slash}USART1_RX)") (class "Default")
      (node (ref "R114") (pin "2") (pinfunction "2_2") (pintype "passive"))
      (node (ref "U100") (pin "46") (pinfunction "PB7/SPI2_MOSI/USART1_RX_46") (pintype "bidirectional"))
    )
    (net (code "45") (name "Net-(U100-PB12{slash}ADC_IN16{slash}FDCAN2_RX)") (class "Default")
      (node (ref "D104") (pin "2") (pinfunction "2_2") (pintype "passive"))
      (node (ref "U100") (pin "24") (pinfunction "PB12/ADC_IN16/FDCAN2_RX_24") (pintype "bidirectional"))
    )
    (net (code "46") (name "Net-(U100-PF0{slash}OSCIN)") (class "Default")
      (node (ref "C100") (pin "1") (pinfunction "1_1") (pintype "passive"))
      (node (ref "U100") (pin "8") (pinfunction "PF0/OSCIN_8") (pintype "passive"))
    )
    (net (code "47") (name "Net-(U100-VREF+)") (class "Default")
      (node (ref "C105") (pin "2") (pinfunction "2_2") (pintype "passive"))
      (node (ref "U100") (pin "5") (pinfunction "VREF+_5") (pintype "passive"))
    )
    (net (code "48") (name "Net-(U102-+Vin)") (class "Default")
      (node (ref "L102") (pin "2") (pinfunction "2_2") (pintype "passive"))
      (node (ref "U102") (pin "1") (pinfunction "+Vin_1") (pintype "power_in"))
    )
    (net (code "49") (name "Net-(U102-+Vout)") (class "Default")
      (node (ref "L101") (pin "1") (pinfunction "1_1") (pintype "passive"))
      (node (ref "U102") (pin "6") (pinfunction "+Vout_6") (pintype "power_in"))
    )
    (net (code "50") (name "Net-(U103-CANH)") (class "Default")
      (node (ref "L103") (pin "3") (pintype "passive"))
      (node (ref "U103") (pin "7") (pinfunction "CANH_7") (pintype "bidirectional"))
    )
    (net (code "51") (name "Net-(U103-CANL)") (class "Default")
      (node (ref "L103") (pin "4") (pintype "passive"))
      (node (ref "U103") (pin "6") (pinfunction "CANL_6") (pintype "bidirectional"))
    )
    (net (code "52") (name "Net-(U103-RXD)") (class "Default")
      (node (ref "U103") (pin "4") (pinfunction "RXD_4") (pintype "output"))
      (node (ref "U104") (pin "6") (pinfunction "INB_6") (pintype "input"))
    )
    (net (code "53") (name "Net-(U103-TXD)") (class "Default")
      (node (ref "U103") (pin "1") (pinfunction "TXD_1") (pintype "input"))
      (node (ref "U104") (pin "7") (pinfunction "OUTA_7") (pintype "output"))
    )
    (net (code "54") (name "Net-(U105-CANH)") (class "Default")
      (node (ref "L104") (pin "3") (pintype "passive"))
      (node (ref "U105") (pin "7") (pinfunction "CANH_7") (pintype "bidirectional"))
    )
    (net (code "55") (name "Net-(U105-CANL)") (class "Default")
      (node (ref "L104") (pin "4") (pintype "passive"))
      (node (ref "U105") (pin "6") (pinfunction "CANL_6") (pintype "bidirectional"))
    )
    (net (code "56") (name "Net-(U105-RXD)") (class "Default")
      (node (ref "U105") (pin "4") (pinfunction "RXD_4") (pintype "output"))
      (node (ref "U106") (pin "6") (pinfunction "INB_6") (pintype "input"))
    )
    (net (code "57") (name "Net-(U105-TXD)") (class "Default")
      (node (ref "U105") (pin "1") (pinfunction "TXD_1") (pintype "input"))
      (node (ref "U106") (pin "7") (pinfunction "OUTA_7") (pintype "output"))
    )
    (net (code "58") (name "Net-(X101-D+)") (class "Default")
      (node (ref "R103") (pin "1") (pinfunction "1_1") (pintype "passive"))
      (node (ref "X101") (pin "3") (pinfunction "D+_3") (pintype "bidirectional"))
    )
    (net (code "59") (name "Net-(X101-D-)") (class "Default")
      (node (ref "R102") (pin "1") (pinfunction "1_1") (pintype "passive"))
      (node (ref "X101") (pin "2") (pinfunction "D-_2") (pintype "bidirectional"))
    )
    (net (code "60") (name "Net-(X101-Shield)") (class "Default")
      (node (ref "R105") (pin "2") (pinfunction "2_2") (pintype "passive"))
      (node (ref "X101") (pin "Shell") (pinfunction "Shield_Shell") (pintype "passive"))
    )
    (net (code "61") (name "unconnected-(G100-NC-Pad1)") (class "Default")
      (node (ref "G100") (pin "1") (pinfunction "NC_1") (pintype "passive"))
    )
    (net (code "62") (name "unconnected-(U100-PA2{slash}ADC_IN2{slash}SPI1_MOSI{slash}USART2_TX-Pad13)") (class "Default")
      (node (ref "U100") (pin "13") (pinfunction "PA2/ADC_IN2/SPI1_MOSI/USART2_TX_13") (pintype "bidirectional"))
    )
    (net (code "63") (name "unconnected-(U100-PA8-Pad28)") (class "Default")
      (node (ref "U100") (pin "28") (pinfunction "PA8_28") (pintype "bidirectional"))
    )
    (net (code "64") (name "unconnected-(U100-PA15{slash}USART2_RX-Pad37)") (class "Default")
      (node (ref "U100") (pin "37") (pinfunction "PA15/USART2_RX_37") (pintype "bidirectional"))
    )
    (net (code "65") (name "unconnected-(U100-PB2{slash}ADC_IN10{slash}SPI2_MISO{slash}USART3_TX-Pad21)") (class "Default")
      (node (ref "U100") (pin "21") (pinfunction "PB2/ADC_IN10/SPI2_MISO/USART3_TX_21") (pintype "bidirectional"))
    )
    (net (code "66") (name "unconnected-(U100-PB3{slash}SPI1_SCK{slash}USART5_TX-Pad42)") (class "Default")
      (node (ref "U100") (pin "42") (pinfunction "PB3/SPI1_SCK/USART5_TX_42") (pintype "bidirectional"))
    )
    (net (code "67") (name "unconnected-(U100-PB10{slash}ADC_IN11{slash}SPI2_SCK{slash}USART3_TX-Pad22)") (class "Default")
      (node (ref "U100") (pin "22") (pinfunction "PB10/ADC_IN11/SPI2_SCK/USART3_TX_22") (pintype "bidirectional"))
    )
    (net (code "68") (name "unconnected-(U100-PB11{slash}ADC_IN15{slash}SPI2_MOSI{slash}USART3_RX-Pad23)") (class "Default")
      (node (ref "U100") (pin "23") (pinfunction "PB11/ADC_IN15/SPI2_MOSI/USART3_RX_23") (pintype "bidirectional"))
    )
    (net (code "69") (name "unconnected-(U100-PB13{slash}SPI2_SCK{slash}FDCAN2_TX-Pad25)") (class "Default")
      (node (ref "U100") (pin "25") (pinfunction "PB13/SPI2_SCK/FDCAN2_TX_25") (pintype "bidirectional"))
    )
    (net (code "70") (name "unconnected-(U100-PB14{slash}SPI2_MISO-Pad26)") (class "Default")
      (node (ref "U100") (pin "26") (pinfunction "PB14/SPI2_MISO_26") (pintype "bidirectional"))
    )
    (net (code "71") (name "unconnected-(U100-PB15{slash}SPI2_MOSI-Pad27)") (class "Default")
      (node (ref "U100") (pin "27") (pinfunction "PB15/SPI2_MOSI_27") (pintype "bidirectional"))
    )
    (net (code "72") (name "unconnected-(U100-PC6-Pad30)") (class "Default")
      (node (ref "U100") (pin "30") (pinfunction "PC6_30") (pintype "bidirectional"))
    )
    (net (code "73") (name "unconnected-(U100-PC7-Pad31)") (class "Default")
      (node (ref "U100") (pin "31") (pinfunction "PC7_31") (pintype "bidirectional"))
    )
    (net (code "74") (name "unconnected-(U100-PC13-Pad1)") (class "Default")
      (node (ref "U100") (pin "1") (pinfunction "PC13_1") (pintype "bidirectional"))
    )
    (net (code "75") (name "unconnected-(U100-PC14{slash}OSC32_IN-Pad2)") (class "Default")
      (node (ref "U100") (pin "2") (pinfunction "PC14/OSC32_IN_2") (pintype "bidirectional"))
    )
    (net (code "76") (name "unconnected-(U100-PC15{slash}OSC32_OUT-Pad3)") (class "Default")
      (node (ref "U100") (pin "3") (pinfunction "PC15/OSC32_OUT_3") (pintype "bidirectional"))
    )
    (net (code "77") (name "unconnected-(U100-PD0{slash}FDCAN1_RX-Pad38)") (class "Default")
      (node (ref "U100") (pin "38") (pinfunction "PD0/FDCAN1_RX_38") (pintype "bidirectional"))
    )
    (net (code "78") (name "unconnected-(U100-PD1{slash}FDCAN1_TX{slash}SPI2_SCK-Pad39)") (class "Default")
      (node (ref "U100") (pin "39") (pinfunction "PD1/FDCAN1_TX/SPI2_SCK_39") (pintype "bidirectional"))
    )
    (net (code "79") (name "unconnected-(U100-PD2{slash}USART5_RX-Pad40)") (class "Default")
      (node (ref "U100") (pin "40") (pinfunction "PD2/USART5_RX_40") (pintype "bidirectional"))
    )
    (net (code "80") (name "unconnected-(U100-PD3{slash}USART5_TX{slash}SPI2_MISO-Pad41)") (class "Default")
      (node (ref "U100") (pin "41") (pinfunction "PD3/USART5_TX/SPI2_MISO_41") (pintype "bidirectional"))
    )
    (net (code "81") (name "unconnected-(U100-PF1{slash}OSCOUT-Pad9)") (class "Default")
      (node (ref "U100") (pin "9") (pinfunction "PF1/OSCOUT_9") (pintype "passive"))
    )
    (net (code "82") (name "unconnected-(X103-Pad4)") (class "Default")
      (node (ref "X103") (pin "4") (pinfunction "4_4") (pintype "passive"))
    )
    (net (code "83") (name "unconnected-(X103-Pad5)") (class "Default")
      (node (ref "X103") (pin "5") (pinfunction "5_5") (pintype "passive"))
    )
    (net (code "84") (name "unconnected-(X103-Pad9)") (class "Default")
      (node (ref "X103") (pin "9") (pinfunction "9_9") (pintype "passive"))
    )
    (net (code "85") (name "unconnected-(X103-PadSH)") (class "Default")
      (node (ref "X103") (pin "SH") (pinfunction "SH_SH") (pintype "passive"))
    )
    (net (code "86") (name "unconnected-(X104-KEY-Pad7)") (class "Default")
      (node (ref "X104") (pin "7") (pinfunction "KEY_7") (pintype "passive"))
    )
    (net (code "87") (name "unconnected-(X104-NC{slash}TDI-Pad8)") (class "Default")
      (node (ref "X104") (pin "8") (pinfunction "NC/TDI_8") (pintype "passive"))
    )
    (net (code "88") (name "unconnected-(X104-SWO{slash}TDO-Pad6)") (class "Default")
      (node (ref "X104") (pin "6") (pinfunction "SWO/TDO_6") (pintype "passive"))
    )
  )
)
